# TEMP_NC_I2C_V1.net
KiCad netlist of a schematic drawn in EAGLE
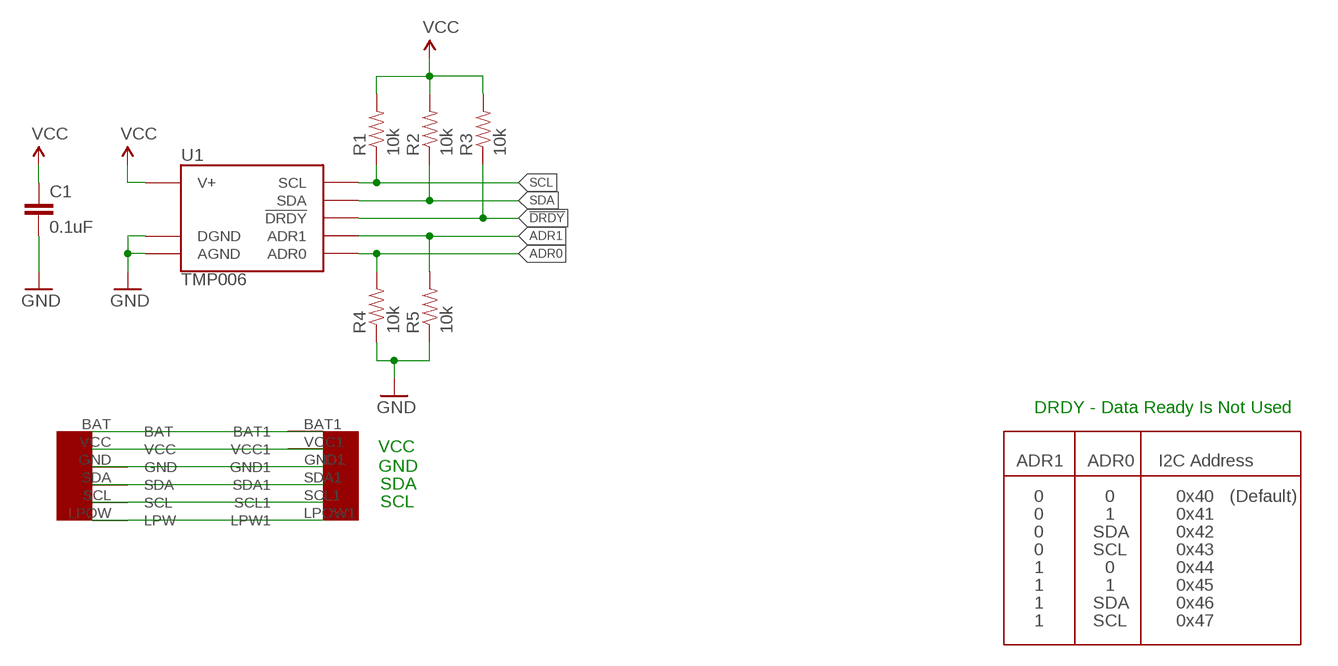
[diagram p0: schematic, sheet 1]

(export (version "E")
  (design (tool "Eeschema 10.0.6"))
  (components
    (comp (ref "C1")
      (value "0.1uF")
      (footprint "eagle-import:0603-CAP")
      (libsource (lib "eagle-import") (part "CAP0603-CAP"))
    )
    (comp (ref "R1")
      (value "10k")
      (footprint "eagle-import:0603-RES")
      (libsource (lib "eagle-import") (part "RESISTOR0603-RES"))
    )
    (comp (ref "R2")
      (value "10k")
      (footprint "eagle-import:0603-RES")
      (libsource (lib "eagle-import") (part "RESISTOR0603-RES"))
    )
    (comp (ref "R3")
      (value "10k")
      (footprint "eagle-import:0603-RES")
      (libsource (lib "eagle-import") (part "RESISTOR0603-RES"))
    )
    (comp (ref "R4")
      (value "10k")
      (footprint "eagle-import:0603-RES")
      (libsource (lib "eagle-import") (part "RESISTOR0603-RES"))
    )
    (comp (ref "R5")
      (value "10k")
      (footprint "eagle-import:0603-RES")
      (libsource (lib "eagle-import") (part "RESISTOR0603-RES"))
    )
    (comp (ref "U$1")
      (value "EASYI2C6PINHEADER")
      (footprint "eagle-import:EASYI2C6PINHEADER")
      (libsource (lib "eagle-import") (part "EASYI2C6PINHEADER"))
    )
    (comp (ref "U1")
      (value "TMP006")
      (footprint "eagle-import:BGA8DS")
      (libsource (lib "eagle-import") (part "TMP006"))
    )
  )
  (nets
    (net (code "1") (name "/~{DRDY}") (class "Default")
      (node (ref "R3") (pin "1") (pinfunction "1_1") (pintype "passive"))
      (node (ref "U1") (pin "C2") (pinfunction "~{DRDY}_C2") (pintype "bidirectional"))
    )
    (net (code "2") (name "ADR0") (class "Default")
      (node (ref "R4") (pin "2") (pinfunction "2_2") (pintype "passive"))
      (node (ref "U1") (pin "C1") (pinfunction "ADR0_C1") (pintype "bidirectional"))
    )
    (net (code "3") (name "ADR1") (class "Default")
      (node (ref "R5") (pin "2") (pinfunction "2_2") (pintype "passive"))
      (node (ref "U1") (pin "B1") (pinfunction "ADR1_B1") (pintype "bidirectional"))
    )
    (net (code "4") (name "GND") (class "Default")
      (node (ref "C1") (pin "2") (pinfunction "2_2") (pintype "passive"))
      (node (ref "R4") (pin "1") (pinfunction "1_1") (pintype "passive"))
      (node (ref "R5") (pin "1") (pinfunction "1_1") (pintype "passive"))
      (node (ref "U$1") (pin "GND") (pinfunction "GND_GND") (pintype "bidirectional"))
      (node (ref "U$1") (pin "GND1") (pinfunction "GND1_GND1") (pintype "bidirectional"))
      (node (ref "U1") (pin "A1") (pinfunction "DGND_A1") (pintype "bidirectional"))
      (node (ref "U1") (pin "A2") (pinfunction "AGND_A2") (pintype "bidirectional"))
    )
    (net (code "5") (name "Net-(U$1-LPW)") (class "Default")
      (node (ref "U$1") (pin "LPOW") (pinfunction "LPW_LPOW") (pintype "bidirectional"))
      (node (ref "U$1") (pin "LPOW1") (pinfunction "LPW1_LPOW1") (pintype "bidirectional"))
    )
    (net (code "6") (name "Net-(U$1-PadBAT)") (class "Default")
      (node (ref "U$1") (pin "BAT") (pinfunction "BAT_BAT") (pintype "bidirectional"))
      (node (ref "U$1") (pin "BAT1") (pinfunction "BAT1_BAT1") (pintype "bidirectional"))
    )
    (net (code "7") (name "SCL") (class "Default")
      (node (ref "R1") (pin "1") (pinfunction "1_1") (pintype "passive"))
      (node (ref "U$1") (pin "SCL") (pinfunction "SCL_SCL") (pintype "bidirectional"))
      (node (ref "U$1") (pin "SCL1") (pinfunction "SCL1_SCL1") (pintype "bidirectional"))
      (node (ref "U1") (pin "B3") (pinfunction "SCL_B3") (pintype "bidirectional"))
    )
    (net (code "8") (name "SDA") (class "Default")
      (node (ref "R2") (pin "1") (pinfunction "1_1") (pintype "passive"))
      (node (ref "U$1") (pin "SDA") (pinfunction "SDA_SDA") (pintype "bidirectional"))
      (node (ref "U$1") (pin "SDA1") (pinfunction "SDA1_SDA1") (pintype "bidirectional"))
      (node (ref "U1") (pin "C3") (pinfunction "SDA_C3") (pintype "bidirectional"))
    )
    (net (code "9") (name "VCC") (class "Default")
      (node (ref "C1") (pin "1") (pinfunction "1_1") (pintype "passive"))
      (node (ref "R1") (pin "2") (pinfunction "2_2") (pintype "passive"))
      (node (ref "R2") (pin "2") (pinfunction "2_2") (pintype "passive"))
      (node (ref "R3") (pin "2") (pinfunction "2_2") (pintype "passive"))
      (node (ref "U$1") (pin "VCC") (pinfunction "VCC_VCC") (pintype "bidirectional"))
      (node (ref "U$1") (pin "VCC1") (pinfunction "VCC1_VCC1") (pintype "bidirectional"))
      (node (ref "U1") (pin "A3") (pinfunction "V+_A3") (pintype "bidirectional"))
    )
  )
)
